# BrewBoard.net
KiCad netlist of a schematic drawn in EAGLE
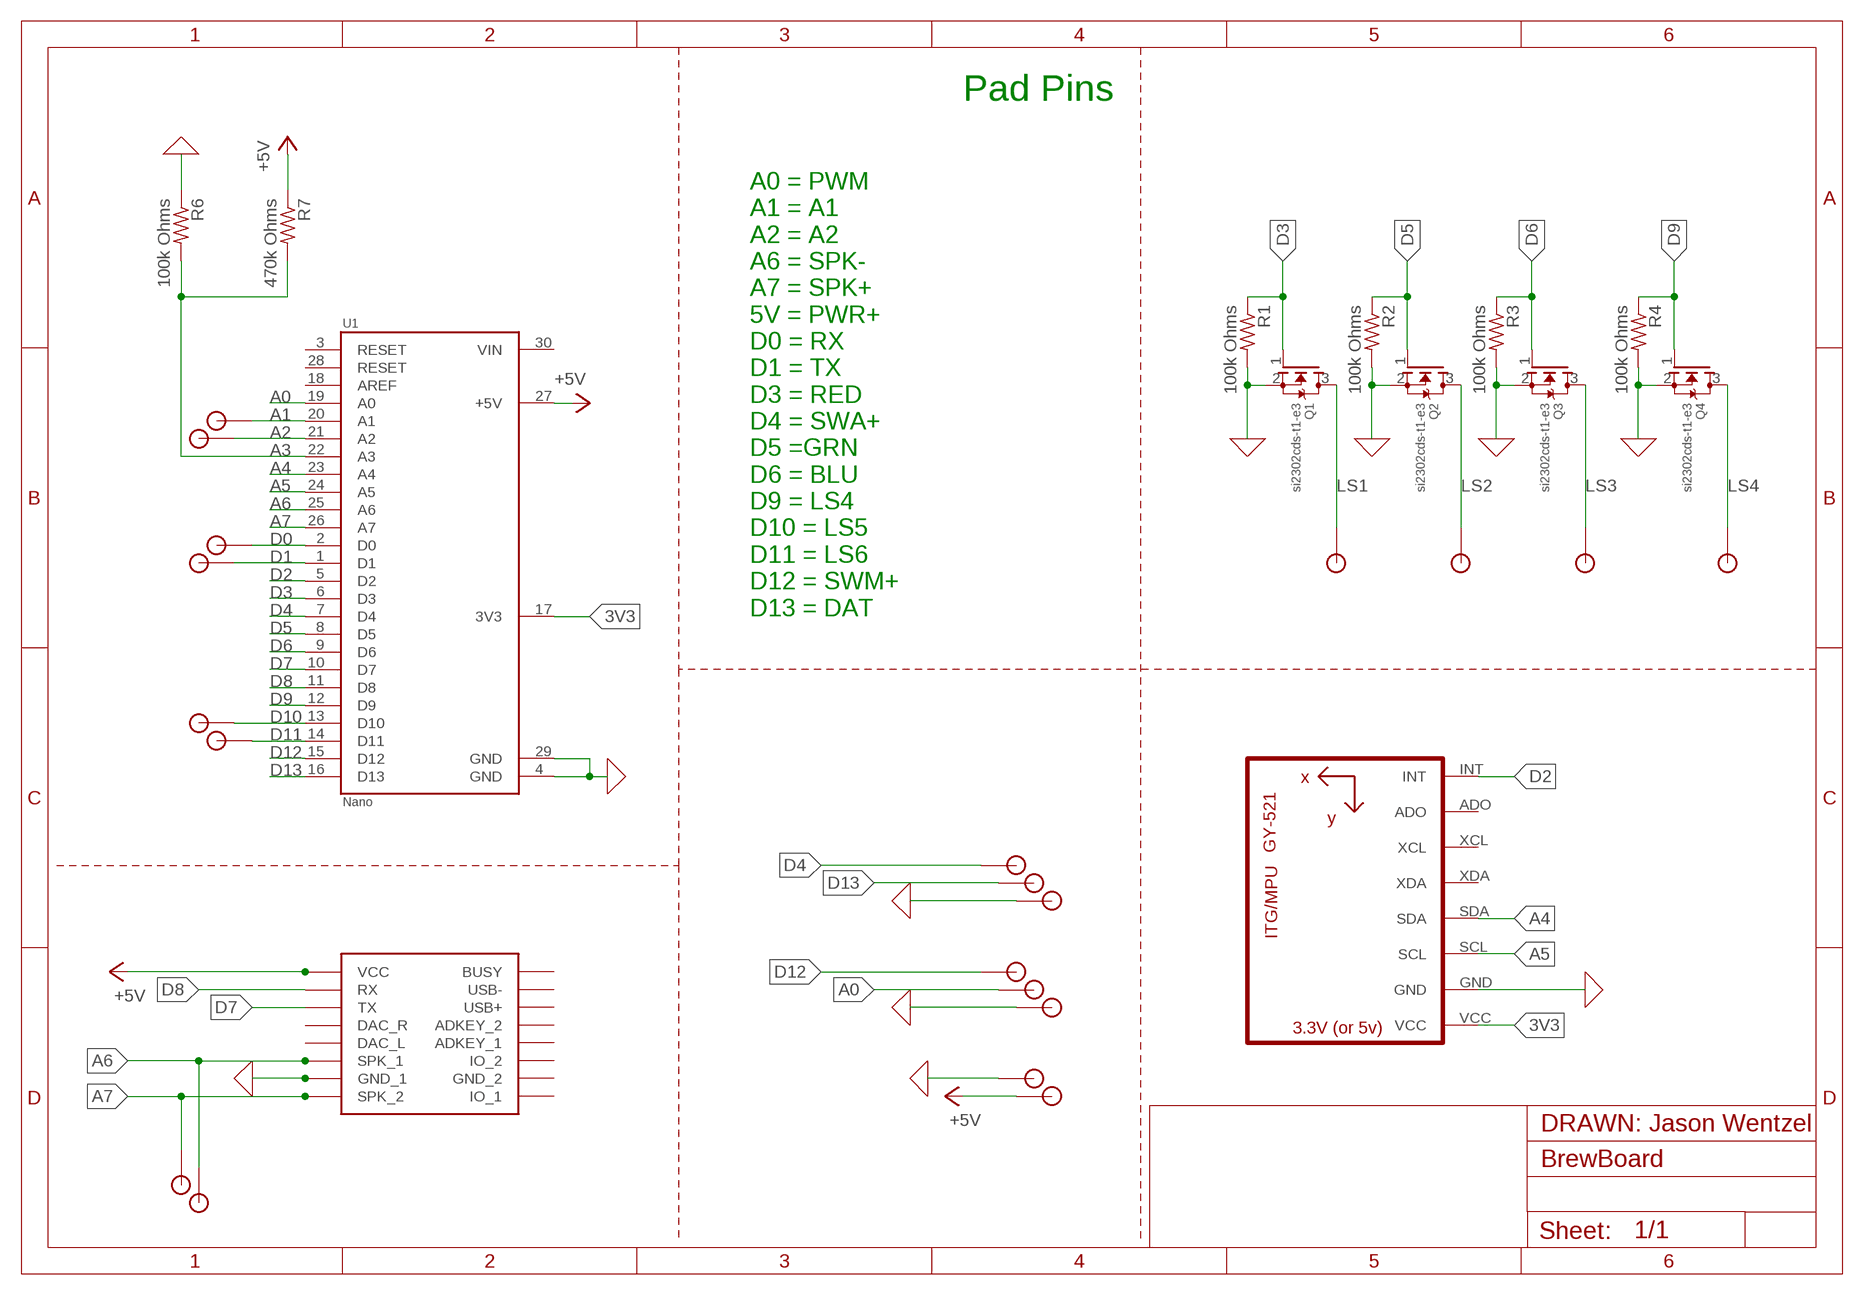
[diagram p0: schematic, sheet 1]

(export (version "E")
  (design (tool "Eeschema 10.0.6"))
  (components
    (comp (ref "LS1")
      (value "SINGLE_ONE_SIDE_PAD")
      (footprint "eagle-import:SOS_PAD")
      (libsource (lib "eagle-import") (part "BrewboardV4_SINGLE_ONE_SIDE_PAD"))
    )
    (comp (ref "Q1")
      (value "si2302cds-t1-e3")
      (footprint "eagle-import:SOT23")
      (libsource (lib "eagle-import") (part "MOSFET-NREFLOW"))
    )
    (comp (ref "Q2")
      (value "si2302cds-t1-e3")
      (footprint "eagle-import:SOT23")
      (libsource (lib "eagle-import") (part "MOSFET-NREFLOW"))
    )
    (comp (ref "Q3")
      (value "si2302cds-t1-e3")
      (footprint "eagle-import:SOT23")
      (libsource (lib "eagle-import") (part "MOSFET-NREFLOW"))
    )
    (comp (ref "Q4")
      (value "si2302cds-t1-e3")
      (footprint "eagle-import:SOT23")
      (libsource (lib "eagle-import") (part "MOSFET-NREFLOW"))
    )
    (comp (ref "R1")
      (value "100k Ohms")
      (footprint "eagle-import:R0805")
      (libsource (lib "eagle-import") (part "R-US_R0805"))
    )
    (comp (ref "R2")
      (value "100k Ohms")
      (footprint "eagle-import:R0805")
      (libsource (lib "eagle-import") (part "R-US_R0805"))
    )
    (comp (ref "R3")
      (value "100k Ohms")
      (footprint "eagle-import:R0805")
      (libsource (lib "eagle-import") (part "R-US_R0805"))
    )
    (comp (ref "R4")
      (value "100k Ohms")
      (footprint "eagle-import:R0805")
      (libsource (lib "eagle-import") (part "R-US_R0805"))
    )
    (comp (ref "R6")
      (value "100k Ohms")
      (footprint "eagle-import:R0805")
      (libsource (lib "eagle-import") (part "R-US_R0805"))
    )
    (comp (ref "R7")
      (value "470k Ohms")
      (footprint "eagle-import:R0805")
      (libsource (lib "eagle-import") (part "R-US_R0805"))
    )
    (comp (ref "SPK+")
      (value "SINGLE_ONE_SIDE_PAD")
      (footprint "eagle-import:SOS_PAD")
      (libsource (lib "eagle-import") (part "BrewboardV4_SINGLE_ONE_SIDE_PAD"))
    )
    (comp (ref "U$1")
      (value "SINGLE_ONE_SIDE_PAD")
      (footprint "eagle-import:SOS_PAD")
      (libsource (lib "eagle-import") (part "BrewboardV4_SINGLE_ONE_SIDE_PAD"))
    )
    (comp (ref "U$4")
      (value "SINGLE_ONE_SIDE_PAD")
      (footprint "eagle-import:SOS_PAD")
      (libsource (lib "eagle-import") (part "BrewboardV4_SINGLE_ONE_SIDE_PAD"))
    )
    (comp (ref "U$5")
      (value "SINGLE_ONE_SIDE_PAD")
      (footprint "eagle-import:SOS_PAD")
      (libsource (lib "eagle-import") (part "BrewboardV4_SINGLE_ONE_SIDE_PAD"))
    )
    (comp (ref "U$6")
      (value "SINGLE_ONE_SIDE_PAD")
      (footprint "eagle-import:SOS_PAD")
      (libsource (lib "eagle-import") (part "BrewboardV4_SINGLE_ONE_SIDE_PAD"))
    )
    (comp (ref "U$7")
      (value "SINGLE_ONE_SIDE_PAD")
      (footprint "eagle-import:SOS_PAD")
      (libsource (lib "eagle-import") (part "BrewboardV4_SINGLE_ONE_SIDE_PAD"))
    )
    (comp (ref "U$8")
      (value "SINGLE_ONE_SIDE_PAD")
      (footprint "eagle-import:SOS_PAD")
      (libsource (lib "eagle-import") (part "BrewboardV4_SINGLE_ONE_SIDE_PAD"))
    )
    (comp (ref "U$9")
      (value "SINGLE_ONE_SIDE_PAD")
      (footprint "eagle-import:SOS_PAD")
      (libsource (lib "eagle-import") (part "BrewboardV4_SINGLE_ONE_SIDE_PAD"))
    )
    (comp (ref "U$11")
      (value "SINGLE_ONE_SIDE_PAD")
      (footprint "eagle-import:SOS_PAD")
      (libsource (lib "eagle-import") (part "BrewboardV4_SINGLE_ONE_SIDE_PAD"))
    )
    (comp (ref "U$12")
      (value "SINGLE_ONE_SIDE_PAD")
      (footprint "eagle-import:SOS_PAD")
      (libsource (lib "eagle-import") (part "BrewboardV4_SINGLE_ONE_SIDE_PAD"))
    )
    (comp (ref "U$13")
      (value "SINGLE_ONE_SIDE_PAD")
      (footprint "eagle-import:SOS_PAD")
      (libsource (lib "eagle-import") (part "BrewboardV4_SINGLE_ONE_SIDE_PAD"))
    )
    (comp (ref "U$15")
      (value "SINGLE_ONE_SIDE_PAD")
      (footprint "eagle-import:SOS_PAD")
      (libsource (lib "eagle-import") (part "BrewboardV4_SINGLE_ONE_SIDE_PAD"))
    )
    (comp (ref "U$16")
      (value "SINGLE_ONE_SIDE_PAD")
      (footprint "eagle-import:SOS_PAD")
      (libsource (lib "eagle-import") (part "BrewboardV4_SINGLE_ONE_SIDE_PAD"))
    )
    (comp (ref "U$17")
      (value "SINGLE_ONE_SIDE_PAD")
      (footprint "eagle-import:SOS_PAD")
      (libsource (lib "eagle-import") (part "BrewboardV4_SINGLE_ONE_SIDE_PAD"))
    )
    (comp (ref "U$18")
      (value "SINGLE_ONE_SIDE_PAD")
      (footprint "eagle-import:SOS_PAD")
      (libsource (lib "eagle-import") (part "BrewboardV4_SINGLE_ONE_SIDE_PAD"))
    )
    (comp (ref "U$19")
      (value "SINGLE_ONE_SIDE_PAD")
      (footprint "eagle-import:SOS_PAD")
      (libsource (lib "eagle-import") (part "BrewboardV4_SINGLE_ONE_SIDE_PAD"))
    )
    (comp (ref "U$22")
      (value "SINGLE_ONE_SIDE_PAD")
      (footprint "eagle-import:SOS_PAD")
      (libsource (lib "eagle-import") (part "BrewboardV4_SINGLE_ONE_SIDE_PAD"))
    )
    (comp (ref "U$27")
      (value "SINGLE_ONE_SIDE_PAD")
      (footprint "eagle-import:SOS_PAD")
      (libsource (lib "eagle-import") (part "BrewboardV4_SINGLE_ONE_SIDE_PAD"))
    )
    (comp (ref "U$28")
      (value "SINGLE_ONE_SIDE_PAD")
      (footprint "eagle-import:SOS_PAD")
      (libsource (lib "eagle-import") (part "BrewboardV4_SINGLE_ONE_SIDE_PAD"))
    )
    (comp (ref "U1")
      (value "Nano")
      (footprint "eagle-import:ARDUINO_NANO_OUT")
      (libsource (lib "eagle-import") (part "A000005NANO_SLIM"))
    )
    (comp (ref "U2")
      (value "GY-521MPU6050")
      (footprint "eagle-import:GY-521")
      (libsource (lib "eagle-import") (part "GY-521MPU6050"))
    )
    (comp (ref "U3")
      (value "DFPLAYER")
      (footprint "eagle-import:DFPLAYER")
      (libsource (lib "eagle-import") (part "DFPLAYER"))
    )
  )
  (nets
    (net (code "1") (name "+5V") (class "Default")
      (node (ref "R7") (pin "1") (pinfunction "1_1") (pintype "passive"))
      (node (ref "U$12") (pin "P$1") (pinfunction "P$1_P$1") (pintype "bidirectional"))
      (node (ref "U1") (pin "27") (pinfunction "+5V_27") (pintype "power_in"))
      (node (ref "U3") (pin "VCC") (pinfunction "VCC_VCC") (pintype "bidirectional"))
    )
    (net (code "2") (name "/A1") (class "Default")
      (node (ref "U$1") (pin "P$1") (pinfunction "P$1_P$1") (pintype "bidirectional"))
      (node (ref "U1") (pin "20") (pinfunction "A1_20") (pintype "input"))
    )
    (net (code "3") (name "/A2") (class "Default")
      (node (ref "U$4") (pin "P$1") (pinfunction "P$1_P$1") (pintype "bidirectional"))
      (node (ref "U1") (pin "21") (pinfunction "A2_21") (pintype "input"))
    )
    (net (code "4") (name "/A3") (class "Default")
      (node (ref "R6") (pin "2") (pinfunction "2_2") (pintype "passive"))
      (node (ref "R7") (pin "2") (pinfunction "2_2") (pintype "passive"))
      (node (ref "U1") (pin "22") (pinfunction "A3_22") (pintype "input"))
    )
    (net (code "5") (name "/D0") (class "Default")
      (node (ref "U$5") (pin "P$1") (pinfunction "P$1_P$1") (pintype "bidirectional"))
      (node (ref "U1") (pin "2") (pinfunction "D0_2") (pintype "bidirectional"))
    )
    (net (code "6") (name "/D1") (class "Default")
      (node (ref "U$6") (pin "P$1") (pinfunction "P$1_P$1") (pintype "bidirectional"))
      (node (ref "U1") (pin "1") (pinfunction "D1_1") (pintype "bidirectional"))
    )
    (net (code "7") (name "/D10") (class "Default")
      (node (ref "U$8") (pin "P$1") (pinfunction "P$1_P$1") (pintype "bidirectional"))
      (node (ref "U1") (pin "13") (pinfunction "D10_13") (pintype "bidirectional"))
    )
    (net (code "8") (name "/D11") (class "Default")
      (node (ref "U$9") (pin "P$1") (pinfunction "P$1_P$1") (pintype "bidirectional"))
      (node (ref "U1") (pin "14") (pinfunction "D11_14") (pintype "bidirectional"))
    )
    (net (code "9") (name "/LS1") (class "Default")
      (node (ref "LS1") (pin "P$1") (pinfunction "P$1_P$1") (pintype "bidirectional"))
      (node (ref "Q1") (pin "3") (pinfunction "D_3") (pintype "bidirectional"))
    )
    (net (code "10") (name "/LS2") (class "Default")
      (node (ref "Q2") (pin "3") (pinfunction "D_3") (pintype "bidirectional"))
      (node (ref "U$15") (pin "P$1") (pinfunction "P$1_P$1") (pintype "bidirectional"))
    )
    (net (code "11") (name "/LS3") (class "Default")
      (node (ref "Q3") (pin "3") (pinfunction "D_3") (pintype "bidirectional"))
      (node (ref "U$16") (pin "P$1") (pinfunction "P$1_P$1") (pintype "bidirectional"))
    )
    (net (code "12") (name "/LS4") (class "Default")
      (node (ref "Q4") (pin "3") (pinfunction "D_3") (pintype "bidirectional"))
      (node (ref "U$7") (pin "P$1") (pinfunction "P$1_P$1") (pintype "bidirectional"))
    )
    (net (code "13") (name "/VIN") (class "Default")
      (node (ref "U1") (pin "30") (pinfunction "VIN_30") (pintype "power_in"))
    )
    (net (code "14") (name "3V3") (class "Default")
      (node (ref "U1") (pin "17") (pinfunction "3V3_17") (pintype "output"))
      (node (ref "U2") (pin "VCC") (pinfunction "VCC_VCC") (pintype "bidirectional"))
    )
    (net (code "15") (name "A0") (class "Default")
      (node (ref "U$18") (pin "P$1") (pinfunction "P$1_P$1") (pintype "bidirectional"))
      (node (ref "U1") (pin "19") (pinfunction "A0_19") (pintype "input"))
    )
    (net (code "16") (name "A4") (class "Default")
      (node (ref "U1") (pin "23") (pinfunction "A4_23") (pintype "input"))
      (node (ref "U2") (pin "SDA") (pinfunction "SDA_SDA") (pintype "bidirectional"))
    )
    (net (code "17") (name "A5") (class "Default")
      (node (ref "U1") (pin "24") (pinfunction "A5_24") (pintype "input"))
      (node (ref "U2") (pin "SCL") (pinfunction "SCL_SCL") (pintype "bidirectional"))
    )
    (net (code "18") (name "A6") (class "Default")
      (node (ref "U$11") (pin "P$1") (pinfunction "P$1_P$1") (pintype "bidirectional"))
      (node (ref "U1") (pin "25") (pinfunction "A6_25") (pintype "input"))
      (node (ref "U3") (pin "SPK1") (pinfunction "SPK_1_SPK1") (pintype "bidirectional"))
    )
    (net (code "19") (name "A7") (class "Default")
      (node (ref "SPK+") (pin "P$1") (pinfunction "P$1_P$1") (pintype "bidirectional"))
      (node (ref "U1") (pin "26") (pinfunction "A7_26") (pintype "input"))
      (node (ref "U3") (pin "SPK2") (pinfunction "SPK_2_SPK2") (pintype "bidirectional"))
    )
    (net (code "20") (name "D2") (class "Default")
      (node (ref "U1") (pin "5") (pinfunction "D2_5") (pintype "bidirectional"))
      (node (ref "U2") (pin "INT") (pinfunction "INT_INT") (pintype "bidirectional"))
    )
    (net (code "21") (name "D3") (class "Default")
      (node (ref "Q1") (pin "1") (pinfunction "G_1") (pintype "bidirectional"))
      (node (ref "R1") (pin "1") (pinfunction "1_1") (pintype "passive"))
      (node (ref "U1") (pin "6") (pinfunction "D3_6") (pintype "bidirectional"))
    )
    (net (code "22") (name "D4") (class "Default")
      (node (ref "U$22") (pin "P$1") (pinfunction "P$1_P$1") (pintype "bidirectional"))
      (node (ref "U1") (pin "7") (pinfunction "D4_7") (pintype "bidirectional"))
    )
    (net (code "23") (name "D5") (class "Default")
      (node (ref "Q2") (pin "1") (pinfunction "G_1") (pintype "bidirectional"))
      (node (ref "R2") (pin "1") (pinfunction "1_1") (pintype "passive"))
      (node (ref "U1") (pin "8") (pinfunction "D5_8") (pintype "bidirectional"))
    )
    (net (code "24") (name "D6") (class "Default")
      (node (ref "Q3") (pin "1") (pinfunction "G_1") (pintype "bidirectional"))
      (node (ref "R3") (pin "1") (pinfunction "1_1") (pintype "passive"))
      (node (ref "U1") (pin "9") (pinfunction "D6_9") (pintype "bidirectional"))
    )
    (net (code "25") (name "D7") (class "Default")
      (node (ref "U1") (pin "10") (pinfunction "D7_10") (pintype "bidirectional"))
      (node (ref "U3") (pin "TX") (pinfunction "TX_TX") (pintype "bidirectional"))
    )
    (net (code "26") (name "D8") (class "Default")
      (node (ref "U1") (pin "11") (pinfunction "D8_11") (pintype "bidirectional"))
      (node (ref "U3") (pin "RX") (pinfunction "RX_RX") (pintype "bidirectional"))
    )
    (net (code "27") (name "D9") (class "Default")
      (node (ref "Q4") (pin "1") (pinfunction "G_1") (pintype "bidirectional"))
      (node (ref "R4") (pin "1") (pinfunction "1_1") (pintype "passive"))
      (node (ref "U1") (pin "12") (pinfunction "D9_12") (pintype "bidirectional"))
    )
    (net (code "28") (name "D12") (class "Default")
      (node (ref "U$19") (pin "P$1") (pinfunction "P$1_P$1") (pintype "bidirectional"))
      (node (ref "U1") (pin "15") (pinfunction "D12_15") (pintype "bidirectional"))
    )
    (net (code "29") (name "D13") (class "Default")
      (node (ref "U$28") (pin "P$1") (pinfunction "P$1_P$1") (pintype "bidirectional"))
      (node (ref "U1") (pin "16") (pinfunction "D13_16") (pintype "bidirectional"))
    )
    (net (code "30") (name "GND") (class "Default")
      (node (ref "Q1") (pin "2") (pinfunction "S_2") (pintype "bidirectional"))
      (node (ref "Q2") (pin "2") (pinfunction "S_2") (pintype "bidirectional"))
      (node (ref "Q3") (pin "2") (pinfunction "S_2") (pintype "bidirectional"))
      (node (ref "Q4") (pin "2") (pinfunction "S_2") (pintype "bidirectional"))
      (node (ref "R1") (pin "2") (pinfunction "2_2") (pintype "passive"))
      (node (ref "R2") (pin "2") (pinfunction "2_2") (pintype "passive"))
      (node (ref "R3") (pin "2") (pinfunction "2_2") (pintype "passive"))
      (node (ref "R4") (pin "2") (pinfunction "2_2") (pintype "passive"))
      (node (ref "R6") (pin "1") (pinfunction "1_1") (pintype "passive"))
      (node (ref "U$13") (pin "P$1") (pinfunction "P$1_P$1") (pintype "bidirectional"))
      (node (ref "U$17") (pin "P$1") (pinfunction "P$1_P$1") (pintype "bidirectional"))
      (node (ref "U$27") (pin "P$1") (pinfunction "P$1_P$1") (pintype "bidirectional"))
      (node (ref "U1") (pin "29") (pinfunction "GND_29") (pintype "power_in"))
      (node (ref "U1") (pin "4") (pinfunction "GND_4") (pintype "power_in"))
      (node (ref "U2") (pin "GND") (pinfunction "GND_GND") (pintype "bidirectional"))
      (node (ref "U3") (pin "GND_1") (pinfunction "GND_1_GND_1") (pintype "bidirectional"))
    )
    (net (code "31") (name "unconnected-(U1-AREF-Pad18)") (class "Default")
      (node (ref "U1") (pin "18") (pinfunction "AREF_18") (pintype "input"))
    )
    (net (code "32") (name "unconnected-(U1-RESET-Pad3)") (class "Default")
      (node (ref "U1") (pin "3") (pinfunction "RESET_3") (pintype "input"))
    )
    (net (code "33") (name "unconnected-(U1-RESET-Pad28)") (class "Default")
      (node (ref "U1") (pin "28") (pinfunction "RESET_28") (pintype "input"))
    )
    (net (code "34") (name "unconnected-(U2-PadADO)") (class "Default")
      (node (ref "U2") (pin "ADO") (pinfunction "ADO_ADO") (pintype "bidirectional"))
    )
    (net (code "35") (name "unconnected-(U2-PadXCL)") (class "Default")
      (node (ref "U2") (pin "XCL") (pinfunction "XCL_XCL") (pintype "bidirectional"))
    )
    (net (code "36") (name "unconnected-(U2-PadXDA)") (class "Default")
      (node (ref "U2") (pin "XDA") (pinfunction "XDA_XDA") (pintype "bidirectional"))
    )
    (net (code "37") (name "unconnected-(U3-ADKEY_1-PadADKEY1)") (class "Default")
      (node (ref "U3") (pin "ADKEY1") (pinfunction "ADKEY_1_ADKEY1") (pintype "bidirectional"))
    )
    (net (code "38") (name "unconnected-(U3-ADKEY_2-PadADKEY2)") (class "Default")
      (node (ref "U3") (pin "ADKEY2") (pinfunction "ADKEY_2_ADKEY2") (pintype "bidirectional"))
    )
    (net (code "39") (name "unconnected-(U3-IO_1-PadIO1)") (class "Default")
      (node (ref "U3") (pin "IO1") (pinfunction "IO_1_IO1") (pintype "bidirectional"))
    )
    (net (code "40") (name "unconnected-(U3-IO_2-PadIO2)") (class "Default")
      (node (ref "U3") (pin "IO2") (pinfunction "IO_2_IO2") (pintype "bidirectional"))
    )
    (net (code "41") (name "unconnected-(U3-PadBUSY)") (class "Default")
      (node (ref "U3") (pin "BUSY") (pinfunction "BUSY_BUSY") (pintype "bidirectional"))
    )
    (net (code "42") (name "unconnected-(U3-PadDAC_L)") (class "Default")
      (node (ref "U3") (pin "DAC_L") (pinfunction "DAC_L_DAC_L") (pintype "bidirectional"))
    )
    (net (code "43") (name "unconnected-(U3-PadDAC_R)") (class "Default")
      (node (ref "U3") (pin "DAC_R") (pinfunction "DAC_R_DAC_R") (pintype "bidirectional"))
    )
    (net (code "44") (name "unconnected-(U3-PadGND_2)") (class "Default")
      (node (ref "U3") (pin "GND_2") (pinfunction "GND_2_GND_2") (pintype "bidirectional"))
    )
    (net (code "45") (name "unconnected-(U3-PadUSB+)") (class "Default")
      (node (ref "U3") (pin "USB+") (pinfunction "USB+_USB+") (pintype "bidirectional"))
    )
    (net (code "46") (name "unconnected-(U3-PadUSB-)") (class "Default")
      (node (ref "U3") (pin "USB-") (pinfunction "USB-_USB-") (pintype "bidirectional"))
    )
  )
)
